# rtc_ds1307_breakout.net
KiCad netlist of a schematic drawn in EAGLE
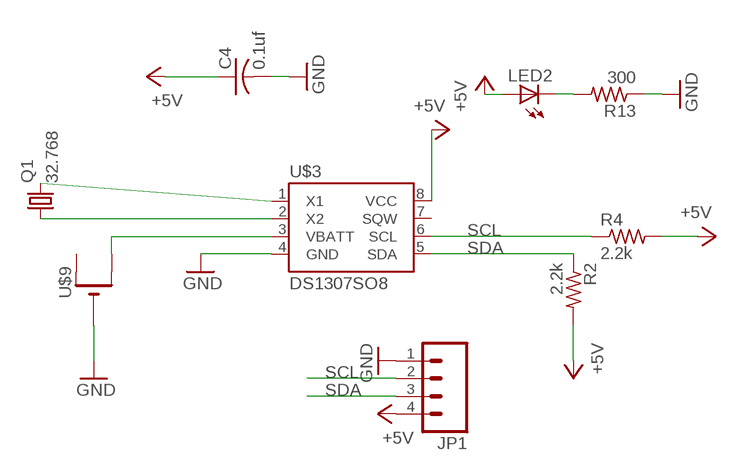
[diagram p0: schematic, sheet 1]

(export (version "E")
  (design (tool "Eeschema 10.0.6"))
  (components
    (comp (ref "C4")
      (value "0.1uf")
      (footprint "eagle-import:C0603")
      (libsource (lib "eagle-import") (part "C-USC0603"))
    )
    (comp (ref "JP1")
      (value "M04LOCK")
      (footprint "eagle-import:1X04_LOCK")
      (libsource (lib "eagle-import") (part "M04LOCK"))
    )
    (comp (ref "LED2")
      (value "LEDCHIPLED_0603")
      (footprint "eagle-import:CHIPLED_0603")
      (libsource (lib "eagle-import") (part "LEDCHIPLED_0603"))
    )
    (comp (ref "Q1")
      (value "32.768")
      (footprint "eagle-import:TC26H")
      (fields (field (name "OC_FARNELL") "unknown") (field (name "OC_NEWARK") "unknown"))
      (libsource (lib "eagle-import") (part "CRYSTALTC26H"))
    )
    (comp (ref "R2")
      (value "2.2k")
      (footprint "eagle-import:R0805")
      (libsource (lib "eagle-import") (part "R-US_R0805"))
    )
    (comp (ref "R4")
      (value "2.2k")
      (footprint "eagle-import:R0805")
      (libsource (lib "eagle-import") (part "R-US_R0805"))
    )
    (comp (ref "R13")
      (value "300")
      (footprint "eagle-import:R0805")
      (libsource (lib "eagle-import") (part "R-US_R0805"))
    )
    (comp (ref "U$3")
      (value "DS1307SO8")
      (footprint "eagle-import:SO08")
      (libsource (lib "eagle-import") (part "DS1307SO8"))
    )
    (comp (ref "U$9")
      (value "CR1220SMT")
      (footprint "eagle-import:CR1220-SMD")
      (libsource (lib "eagle-import") (part "CR1220SMT"))
    )
  )
  (nets
    (net (code "1") (name "+5V") (class "Default")
      (node (ref "C4") (pin "1") (pinfunction "1_1") (pintype "passive"))
      (node (ref "JP1") (pin "4") (pinfunction "4_4") (pintype "passive"))
      (node (ref "LED2") (pin "A") (pinfunction "A_A") (pintype "passive"))
      (node (ref "R2") (pin "2") (pinfunction "2_2") (pintype "passive"))
      (node (ref "R4") (pin "2") (pinfunction "2_2") (pintype "passive"))
      (node (ref "U$3") (pin "8") (pinfunction "VCC_8") (pintype "bidirectional"))
    )
    (net (code "2") (name "/SCL") (class "Default")
      (node (ref "JP1") (pin "2") (pinfunction "2_2") (pintype "passive"))
      (node (ref "R4") (pin "1") (pinfunction "1_1") (pintype "passive"))
      (node (ref "U$3") (pin "6") (pinfunction "SCL_6") (pintype "bidirectional"))
    )
    (net (code "3") (name "/SDA") (class "Default")
      (node (ref "JP1") (pin "3") (pinfunction "3_3") (pintype "passive"))
      (node (ref "R2") (pin "1") (pinfunction "1_1") (pintype "passive"))
      (node (ref "U$3") (pin "5") (pinfunction "SDA_5") (pintype "bidirectional"))
    )
    (net (code "4") (name "GND") (class "Default")
      (node (ref "C4") (pin "2") (pinfunction "2_2") (pintype "passive"))
      (node (ref "JP1") (pin "1") (pinfunction "1_1") (pintype "passive"))
      (node (ref "R13") (pin "1") (pinfunction "1_1") (pintype "passive"))
      (node (ref "U$3") (pin "4") (pinfunction "GND_4") (pintype "bidirectional"))
      (node (ref "U$9") (pin "-") (pinfunction "-_-") (pintype "passive"))
    )
    (net (code "5") (name "Net-(LED2-PadC)") (class "Default")
      (node (ref "LED2") (pin "C") (pinfunction "C_C") (pintype "passive"))
      (node (ref "R13") (pin "2") (pinfunction "2_2") (pintype "passive"))
    )
    (net (code "6") (name "Net-(U$3-VBATT)") (class "Default")
      (node (ref "U$3") (pin "3") (pinfunction "VBATT_3") (pintype "bidirectional"))
      (node (ref "U$9") (pin "+$2") (pinfunction "+1_+$2") (pintype "passive"))
    )
    (net (code "7") (name "Net-(U$3-X1)") (class "Default")
      (node (ref "Q1") (pin "2") (pinfunction "2_2") (pintype "passive"))
      (node (ref "U$3") (pin "1") (pinfunction "X1_1") (pintype "bidirectional"))
    )
    (net (code "8") (name "Net-(U$3-X2)") (class "Default")
      (node (ref "Q1") (pin "1") (pinfunction "1_1") (pintype "passive"))
      (node (ref "U$3") (pin "2") (pinfunction "X2_2") (pintype "bidirectional"))
    )
    (net (code "9") (name "unconnected-(U$3-SQW-Pad7)") (class "Default")
      (node (ref "U$3") (pin "7") (pinfunction "SQW_7") (pintype "bidirectional"))
    )
    (net (code "10") (name "unconnected-(U$9-+-Pad+$1)") (class "Default")
      (node (ref "U$9") (pin "+$1") (pinfunction "+_+$1") (pintype "passive"))
    )
  )
)
